# Principal_Node.net
KiCad netlist of a schematic drawn in Altium Designer
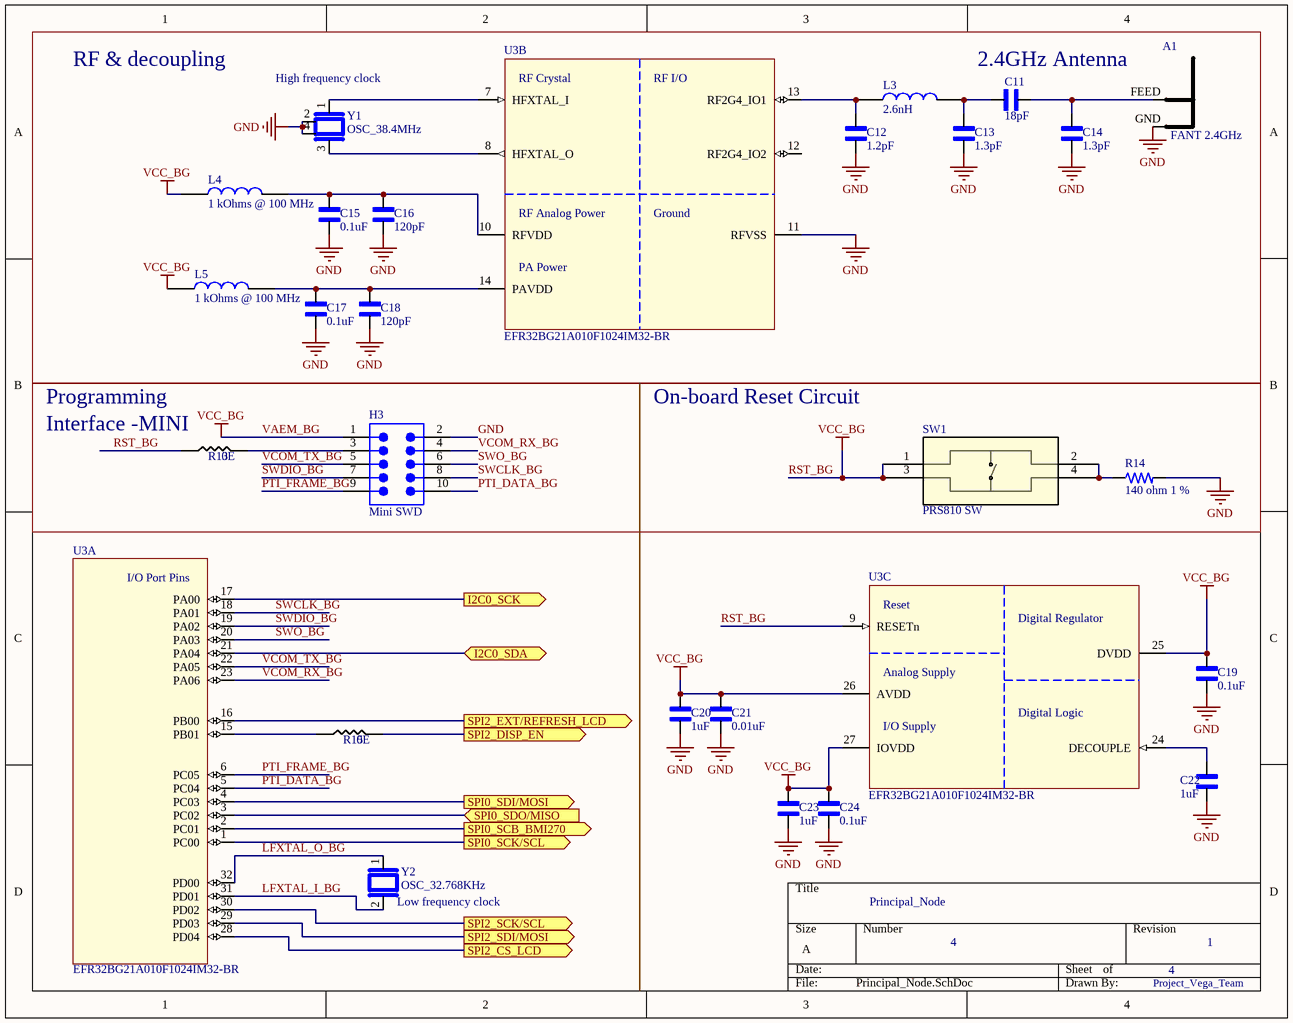
[diagram p0: Principal_Node.SchDoc]

(export (version "E")
  (design (tool "Eeschema 10.0.6"))
  (components
    (comp (ref "A1")
      (value "FANT 2.4GHz")
      (footprint "FANT_2P4")
      (description "Inverted F antenna")
      (libsource (lib "Project_Vega") (part "FANT_2P4"))
    )
    (comp (ref "C11")
      (value "18pF")
      (footprint "CAPC1608X90")
      (description "0.1 ÂµF Â±10% 50V Ceramic Capacitor X7R 0603 (1608 Metric)")
      (fields (field (name "MF") "Yageo") (field (name "MP") "CC0603KRX7R9BB104"))
      (libsource (lib "") (part "CC0603KRX7R9BB104_1"))
    )
    (comp (ref "C12")
      (value "1.2pF")
      (footprint "CAPC1608X90")
      (description "0.1 ÂµF Â±10% 50V Ceramic Capacitor X7R 0603 (1608 Metric)")
      (fields (field (name "MF") "Yageo") (field (name "MP") "CC0603KRX7R9BB104"))
      (libsource (lib "Project_Vega") (part "CC0603KRX7R9BB104"))
    )
    (comp (ref "C13")
      (value "1.3pF")
      (footprint "CAPC1608X90")
      (description "0.1 ÂµF Â±10% 50V Ceramic Capacitor X7R 0603 (1608 Metric)")
      (fields (field (name "MF") "Yageo") (field (name "MP") "CC0603KRX7R9BB104"))
      (libsource (lib "Project_Vega") (part "CC0603KRX7R9BB104"))
    )
    (comp (ref "C14")
      (value "1.3pF")
      (footprint "CAPC1608X90")
      (description "0.1 ÂµF Â±10% 50V Ceramic Capacitor X7R 0603 (1608 Metric)")
      (fields (field (name "MF") "Yageo") (field (name "MP") "CC0603KRX7R9BB104"))
      (libsource (lib "Project_Vega") (part "CC0603KRX7R9BB104"))
    )
    (comp (ref "C15")
      (value "0.1uF")
      (footprint "CAPC1608X90")
      (description "0.1 ÂµF Â±10% 50V Ceramic Capacitor X7R 0603 (1608 Metric)")
      (fields (field (name "MF") "Yageo") (field (name "MP") "CC0603KRX7R9BB104"))
      (libsource (lib "Project_Vega") (part "CC0603KRX7R9BB104"))
    )
    (comp (ref "C16")
      (value "120pF")
      (footprint "CAPC1608X90")
      (description "0.1 ÂµF Â±10% 50V Ceramic Capacitor X7R 0603 (1608 Metric)")
      (fields (field (name "MF") "Yageo") (field (name "MP") "CC0603KRX7R9BB104"))
      (libsource (lib "Project_Vega") (part "CC0603KRX7R9BB104"))
    )
    (comp (ref "C17")
      (value "0.1uF")
      (footprint "CAPC1608X90")
      (description "0.1 ÂµF Â±10% 50V Ceramic Capacitor X7R 0603 (1608 Metric)")
      (fields (field (name "MF") "Yageo") (field (name "MP") "CC0603KRX7R9BB104"))
      (libsource (lib "Project_Vega") (part "CC0603KRX7R9BB104"))
    )
    (comp (ref "C18")
      (value "120pF")
      (footprint "CAPC1608X90")
      (description "0.1 ÂµF Â±10% 50V Ceramic Capacitor X7R 0603 (1608 Metric)")
      (fields (field (name "MF") "Yageo") (field (name "MP") "CC0603KRX7R9BB104"))
      (libsource (lib "Project_Vega") (part "CC0603KRX7R9BB104"))
    )
    (comp (ref "C19")
      (value "0.1uF")
      (footprint "CAPC1608X90")
      (description "0.1 ÂµF Â±10% 50V Ceramic Capacitor X7R 0603 (1608 Metric)")
      (fields (field (name "MF") "Yageo") (field (name "MP") "CC0603KRX7R9BB104"))
      (libsource (lib "Project_Vega") (part "CC0603KRX7R9BB104"))
    )
    (comp (ref "C20")
      (value "1uF")
      (footprint "CAPC1608X90")
      (description "0.1 ÂµF Â±10% 50V Ceramic Capacitor X7R 0603 (1608 Metric)")
      (fields (field (name "MF") "Yageo") (field (name "MP") "CC0603KRX7R9BB104"))
      (libsource (lib "Project_Vega") (part "CC0603KRX7R9BB104"))
    )
    (comp (ref "C21")
      (value "0.01uF")
      (footprint "CAPC1608X90")
      (description "0.1 ÂµF Â±10% 50V Ceramic Capacitor X7R 0603 (1608 Metric)")
      (fields (field (name "MF") "Yageo") (field (name "MP") "CC0603KRX7R9BB104"))
      (libsource (lib "Project_Vega") (part "CC0603KRX7R9BB104"))
    )
    (comp (ref "C22")
      (value "1uF")
      (footprint "CAPC1608X90")
      (description "0.1 ÂµF Â±10% 50V Ceramic Capacitor X7R 0603 (1608 Metric)")
      (fields (field (name "MF") "Yageo") (field (name "MP") "CC0603KRX7R9BB104"))
      (libsource (lib "Project_Vega") (part "CC0603KRX7R9BB104"))
    )
    (comp (ref "C23")
      (value "1uF")
      (footprint "CAPC1608X90")
      (description "0.1 ÂµF Â±10% 50V Ceramic Capacitor X7R 0603 (1608 Metric)")
      (fields (field (name "MF") "Yageo") (field (name "MP") "CC0603KRX7R9BB104"))
      (libsource (lib "Project_Vega") (part "CC0603KRX7R9BB104"))
    )
    (comp (ref "C24")
      (value "0.1uF")
      (footprint "CAPC1608X90")
      (description "0.1 ÂµF Â±10% 50V Ceramic Capacitor X7R 0603 (1608 Metric)")
      (fields (field (name "MF") "Yageo") (field (name "MP") "CC0603KRX7R9BB104"))
      (libsource (lib "Project_Vega") (part "CC0603KRX7R9BB104"))
    )
    (comp (ref "H3")
      (value "Mini SWD")
      (footprint "FTSH-105-01-XXX-DV-K")
      (description "Mini SWD 0.05\" Pitch Connector - 10 Pin SMT Box Header")
      (fields
        (field (name "MANUFACTURER") "Adafruit Industries")
        (field (name "MANUFACTURER PART NUMBER") "4048")
      )
      (libsource (lib "Connectors") (part "Debug Connector Mini SWD - 0.05{dblquote}"))
    )
    (comp (ref "L3")
      (value "2.6nH")
      (footprint "INDC1608X95N")
      (description "Inductor with Inductance 10uH Tol.+/-20% Package 0603 (1608)")
      (fields (field (name "MP") "LQM18DN100M70L") (field (name "MF") "Murata Electronics"))
      (libsource (lib "Project_Vega") (part "LQM18DN100M70L"))
    )
    (comp (ref "L4")
      (value "1 kOhms @ 100 MHz")
      (footprint "INDC1608X95N")
      (description "Inductor with Inductance 10uH Tol.+/-20% Package 0603 (1608)")
      (fields (field (name "MP") "LQM18DN100M70L") (field (name "MF") "Murata Electronics"))
      (libsource (lib "Project_Vega") (part "LQM18DN100M70L"))
    )
    (comp (ref "L5")
      (value "1 kOhms @ 100 MHz")
      (footprint "INDC1608X95N")
      (description "Inductor with Inductance 10uH Tol.+/-20% Package 0603 (1608)")
      (fields (field (name "MP") "LQM18DN100M70L") (field (name "MF") "Murata Electronics"))
      (libsource (lib "Project_Vega") (part "LQM18DN100M70L"))
    )
    (comp (ref "R13")
      (value "0E")
      (footprint "1206_Passive_Resitor")
      (description "10 kOhms ±5% 0.25W, 1/4W Chip Resistor 1206 (3216 Metric) Automotive AEC-Q200 Thick Film")
      (fields (field (name "MFR PART #") "RMCF1206FT10K0") (field (name "LCSC PART#") "C17902"))
      (libsource (lib "ECEN5730Lib_2023_05_DS") (part "R_10KOhm_1206"))
    )
    (comp (ref "R14")
      (value "140 ohm 1 %")
      (footprint "RES_0603_1608X06")
      (description "SMD Chip Resistor, 140 Ohm, ± 1%, 100 mW, 0603 [1608 Metric], Thick Film, General Purpose")
      (fields
        (field (name "MANUFACTURER") "Yageo")
        (field (name "MANUFACTURER PART NUMBER") "RC0603FR-07140RL")
      )
      (libsource (lib "Project_Vega") (part "RC0603FR-07140RL"))
    )
    (comp (ref "R15")
      (value "0E")
      (footprint "1206_Passive_Resitor")
      (description "10 kOhms ±5% 0.25W, 1/4W Chip Resistor 1206 (3216 Metric) Automotive AEC-Q200 Thick Film")
      (fields (field (name "MFR PART #") "RMCF1206FT10K0") (field (name "LCSC PART#") "C17902"))
      (libsource (lib "ECEN5730Lib_2023_05_DS") (part "R_10KOhm_1206"))
    )
    (comp (ref "SW1")
      (value "PRS810 SW")
      (footprint "PTS810_CNK")
      (description "Switch Tactile N.O. SPST Button J-Bend 0.05A 16V 150000Cycles 1.569N SMD T/R")
      (fields
        (field (name "MANUFACTURER") "ITT C&K")
        (field (name "MANUFACTURER PART NUMBER") "PTS810SJM250SMTRLFS")
      )
      (libsource (lib "Project_Vega") (part "PTS810SJM250SMTRLFS"))
    )
    (comp (ref "U3")
      (value "EFR32BG21A010F1024IM32-BR")
      (footprint "QFN32-EFR32xG2xIM32-BR")
      (description "Blue Gecko, QFN32, 2.4G, 10dB, Bluetooth 5.1, 1024kB, 96kB(RAM), 20 GPIO")
      (fields (field (name "MANUFACTURER") "Silicon Labs"))
      (libsource (lib "Project_Vega") (part "EFR32BG21A010F1024IM32-BR"))
    )
    (comp (ref "Y1")
      (value "OSC_38.4MHz")
      (footprint "OSC_38.4MHz")
      (description "38.4 MHz ±10ppm Crystal 10pF 40 Ohms 4-SMD, No Lead")
      (fields
        (field (name "MF") "{'manufacturer': u'Murata Electronics'}")
        (field (name "MP") "XRCGB38M400F2P00R0")
      )
      (libsource (lib "Project_Vega") (part "OSC_38.4MHz"))
    )
    (comp (ref "Y2")
      (value "OSC_32.768KHz")
      (footprint "OSC_32.768KHz")
      (description "Tuning Fork Crystal 32.768kHz in 1.2 x 2.0mm package")
      (fields (field (name "MF") "Micro Crystal") (field (name "MP") "CM8V-T1A-32.768KHZ-7PF-20PPM-TA-QC"))
      (libsource (lib "Project_Vega") (part "OSC_32.768KHz"))
    )
  )
  (nets
    (net (code "1") (name "/I2C0_SCK") (class "Default")
      (node (ref "U3") (pin "17") (pinfunction "PA00_17") (pintype "bidirectional"))
    )
    (net (code "2") (name "/I2C0_SDA") (class "Default")
      (node (ref "U3") (pin "21") (pinfunction "PA04_21") (pintype "bidirectional"))
    )
    (net (code "3") (name "/LFXTAL_I_BG") (class "Default")
      (node (ref "U3") (pin "31") (pinfunction "PD01_31") (pintype "bidirectional"))
      (node (ref "Y2") (pin "2") (pinfunction "2_2") (pintype "passive"))
    )
    (net (code "4") (name "/LFXTAL_O_BG") (class "Default")
      (node (ref "U3") (pin "32") (pinfunction "PD00_32") (pintype "bidirectional"))
      (node (ref "Y2") (pin "1") (pinfunction "1_1") (pintype "passive"))
    )
    (net (code "5") (name "/PTI_DATA_BG") (class "Default")
      (node (ref "H3") (pin "10") (pinfunction "10_10") (pintype "passive"))
      (node (ref "U3") (pin "5") (pinfunction "PC04_5") (pintype "bidirectional"))
    )
    (net (code "6") (name "/PTI_FRAME_BG") (class "Default")
      (node (ref "H3") (pin "9") (pinfunction "9_9") (pintype "passive"))
      (node (ref "U3") (pin "6") (pinfunction "PC05_6") (pintype "bidirectional"))
    )
    (net (code "7") (name "/SPI0_SCB_BMI270") (class "Default")
      (node (ref "U3") (pin "2") (pinfunction "PC01_2") (pintype "bidirectional"))
    )
    (net (code "8") (name "/SPI0_SCK{slash}SCL") (class "Default")
      (node (ref "U3") (pin "1") (pinfunction "PC00_1") (pintype "bidirectional"))
    )
    (net (code "9") (name "/SPI0_SDI{slash}MOSI") (class "Default")
      (node (ref "U3") (pin "4") (pinfunction "PC03_4") (pintype "bidirectional"))
    )
    (net (code "10") (name "/SPI0_SDO{slash}MISO") (class "Default")
      (node (ref "U3") (pin "3") (pinfunction "PC02_3") (pintype "bidirectional"))
    )
    (net (code "11") (name "/SPI2_CS_LCD") (class "Default")
      (node (ref "U3") (pin "28") (pinfunction "PD04_28") (pintype "bidirectional"))
    )
    (net (code "12") (name "/SPI2_DISP_EN") (class "Default")
      (node (ref "R15") (pin "2") (pinfunction "2_2") (pintype "passive"))
    )
    (net (code "13") (name "/SPI2_EXT{slash}REFRESH_LCD") (class "Default")
      (node (ref "U3") (pin "16") (pinfunction "PB00_16") (pintype "bidirectional"))
    )
    (net (code "14") (name "/SPI2_SCK{slash}SCL") (class "Default")
      (node (ref "U3") (pin "30") (pinfunction "PD02_30") (pintype "bidirectional"))
    )
    (net (code "15") (name "/SPI2_SDI{slash}MOSI") (class "Default")
      (node (ref "U3") (pin "29") (pinfunction "PD03_29") (pintype "bidirectional"))
    )
    (net (code "16") (name "/SWCLK_BG") (class "Default")
      (node (ref "H3") (pin "8") (pinfunction "8_8") (pintype "passive"))
      (node (ref "U3") (pin "18") (pinfunction "PA01_18") (pintype "bidirectional"))
    )
    (net (code "17") (name "/SWDIO_BG") (class "Default")
      (node (ref "H3") (pin "7") (pinfunction "7_7") (pintype "passive"))
      (node (ref "U3") (pin "19") (pinfunction "PA02_19") (pintype "bidirectional"))
    )
    (net (code "18") (name "/SWO_BG") (class "Default")
      (node (ref "H3") (pin "6") (pinfunction "6_6") (pintype "passive"))
      (node (ref "U3") (pin "20") (pinfunction "PA03_20") (pintype "bidirectional"))
    )
    (net (code "19") (name "/VCOM_RX_BG") (class "Default")
      (node (ref "H3") (pin "4") (pinfunction "4_4") (pintype "passive"))
      (node (ref "U3") (pin "23") (pinfunction "PA06_23") (pintype "bidirectional"))
    )
    (net (code "20") (name "/VCOM_TX_BG") (class "Default")
      (node (ref "H3") (pin "5") (pinfunction "5_5") (pintype "passive"))
      (node (ref "U3") (pin "22") (pinfunction "PA05_22") (pintype "bidirectional"))
    )
    (net (code "21") (name "GND") (class "Default")
      (node (ref "A1") (pin "GND") (pinfunction "6_GND") (pintype "passive"))
      (node (ref "C12") (pin "2") (pinfunction "2_2") (pintype "passive"))
      (node (ref "C13") (pin "2") (pinfunction "2_2") (pintype "passive"))
      (node (ref "C14") (pin "2") (pinfunction "2_2") (pintype "passive"))
      (node (ref "C15") (pin "2") (pinfunction "2_2") (pintype "passive"))
      (node (ref "C16") (pin "2") (pinfunction "2_2") (pintype "passive"))
      (node (ref "C17") (pin "2") (pinfunction "2_2") (pintype "passive"))
      (node (ref "C18") (pin "2") (pinfunction "2_2") (pintype "passive"))
      (node (ref "C19") (pin "2") (pinfunction "2_2") (pintype "passive"))
      (node (ref "C20") (pin "2") (pinfunction "2_2") (pintype "passive"))
      (node (ref "C21") (pin "2") (pinfunction "2_2") (pintype "passive"))
      (node (ref "C22") (pin "2") (pinfunction "2_2") (pintype "passive"))
      (node (ref "C23") (pin "2") (pinfunction "2_2") (pintype "passive"))
      (node (ref "C24") (pin "2") (pinfunction "2_2") (pintype "passive"))
      (node (ref "H3") (pin "2") (pinfunction "2_2") (pintype "passive"))
      (node (ref "R14") (pin "2") (pinfunction "2_2") (pintype "passive"))
      (node (ref "U3") (pin "11") (pinfunction "RFVSS_11") (pintype "power_in"))
      (node (ref "Y1") (pin "2") (pinfunction "2_2") (pintype "passive"))
      (node (ref "Y1") (pin "4") (pinfunction "4_4") (pintype "passive"))
    )
    (net (code "22") (name "Net-(A1-6-PadFEED)") (class "Default")
      (node (ref "A1") (pin "FEED") (pinfunction "6_FEED") (pintype "passive"))
      (node (ref "C11") (pin "2") (pinfunction "2_2") (pintype "passive"))
      (node (ref "C14") (pin "1") (pinfunction "1_1") (pintype "passive"))
    )
    (net (code "23") (name "Net-(C11-Pad1)") (class "Default")
      (node (ref "C11") (pin "1") (pinfunction "1_1") (pintype "passive"))
      (node (ref "C13") (pin "1") (pinfunction "1_1") (pintype "passive"))
      (node (ref "L3") (pin "2") (pinfunction "2_2") (pintype "passive"))
    )
    (net (code "24") (name "Net-(H3-Pad3)") (class "Default")
      (node (ref "H3") (pin "3") (pinfunction "3_3") (pintype "passive"))
      (node (ref "R13") (pin "2") (pinfunction "2_2") (pintype "passive"))
    )
    (net (code "25") (name "Net-(R14-Pad1)") (class "Default")
      (node (ref "R14") (pin "1") (pinfunction "1_1") (pintype "passive"))
      (node (ref "SW1") (pin "2") (pinfunction "2_2") (pintype "passive"))
      (node (ref "SW1") (pin "4") (pinfunction "4_4") (pintype "passive"))
    )
    (net (code "26") (name "Net-(U3A-PB01)") (class "Default")
      (node (ref "R15") (pin "1") (pinfunction "1_1") (pintype "passive"))
      (node (ref "U3") (pin "15") (pinfunction "PB01_15") (pintype "bidirectional"))
    )
    (net (code "27") (name "Net-(U3B-HFXTAL_I)") (class "Default")
      (node (ref "U3") (pin "7") (pinfunction "HFXTAL_I_7") (pintype "input"))
      (node (ref "Y1") (pin "1") (pinfunction "1_1") (pintype "passive"))
    )
    (net (code "28") (name "Net-(U3B-HFXTAL_O)") (class "Default")
      (node (ref "U3") (pin "8") (pinfunction "HFXTAL_O_8") (pintype "output"))
      (node (ref "Y1") (pin "3") (pinfunction "3_3") (pintype "passive"))
    )
    (net (code "29") (name "Net-(U3B-PAVDD)") (class "Default")
      (node (ref "C17") (pin "1") (pinfunction "1_1") (pintype "passive"))
      (node (ref "C18") (pin "1") (pinfunction "1_1") (pintype "passive"))
      (node (ref "L5") (pin "2") (pinfunction "2_2") (pintype "passive"))
      (node (ref "U3") (pin "14") (pinfunction "PAVDD_14") (pintype "power_in"))
    )
    (net (code "30") (name "Net-(U3B-RF2G4_IO1)") (class "Default")
      (node (ref "C12") (pin "1") (pinfunction "1_1") (pintype "passive"))
      (node (ref "L3") (pin "1") (pinfunction "1_1") (pintype "passive"))
      (node (ref "U3") (pin "13") (pinfunction "RF2G4_IO1_13") (pintype "bidirectional"))
    )
    (net (code "31") (name "Net-(U3B-RFVDD)") (class "Default")
      (node (ref "C15") (pin "1") (pinfunction "1_1") (pintype "passive"))
      (node (ref "C16") (pin "1") (pinfunction "1_1") (pintype "passive"))
      (node (ref "L4") (pin "2") (pinfunction "2_2") (pintype "passive"))
      (node (ref "U3") (pin "10") (pinfunction "RFVDD_10") (pintype "power_in"))
    )
    (net (code "32") (name "Net-(U3C-DECOUPLE)") (class "Default")
      (node (ref "C22") (pin "1") (pinfunction "1_1") (pintype "passive"))
      (node (ref "U3") (pin "24") (pinfunction "DECOUPLE_24") (pintype "input"))
    )
    (net (code "33") (name "VCC_BG") (class "Default")
      (node (ref "C19") (pin "1") (pinfunction "1_1") (pintype "passive"))
      (node (ref "C20") (pin "1") (pinfunction "1_1") (pintype "passive"))
      (node (ref "C21") (pin "1") (pinfunction "1_1") (pintype "passive"))
      (node (ref "C23") (pin "1") (pinfunction "1_1") (pintype "passive"))
      (node (ref "C24") (pin "1") (pinfunction "1_1") (pintype "passive"))
      (node (ref "H3") (pin "1") (pinfunction "1_1") (pintype "passive"))
      (node (ref "L4") (pin "1") (pinfunction "1_1") (pintype "passive"))
      (node (ref "L5") (pin "1") (pinfunction "1_1") (pintype "passive"))
      (node (ref "R13") (pin "1") (pinfunction "1_1") (pintype "passive"))
      (node (ref "SW1") (pin "1") (pinfunction "1_1") (pintype "passive"))
      (node (ref "SW1") (pin "3") (pinfunction "3_3") (pintype "passive"))
      (node (ref "U3") (pin "25") (pinfunction "DVDD_25") (pintype "power_in"))
      (node (ref "U3") (pin "26") (pinfunction "AVDD_26") (pintype "power_in"))
      (node (ref "U3") (pin "27") (pinfunction "IOVDD_27") (pintype "power_in"))
      (node (ref "U3") (pin "9") (pinfunction "RESETn_9") (pintype "input"))
    )
    (net (code "34") (name "unconnected-(U3B-RF2G4_IO2-Pad12)") (class "Default")
      (node (ref "U3") (pin "12") (pinfunction "RF2G4_IO2_12") (pintype "bidirectional"))
    )
  )
)
